# Emoji_Board_v2.net
KiCad netlist of a schematic drawn in EAGLE
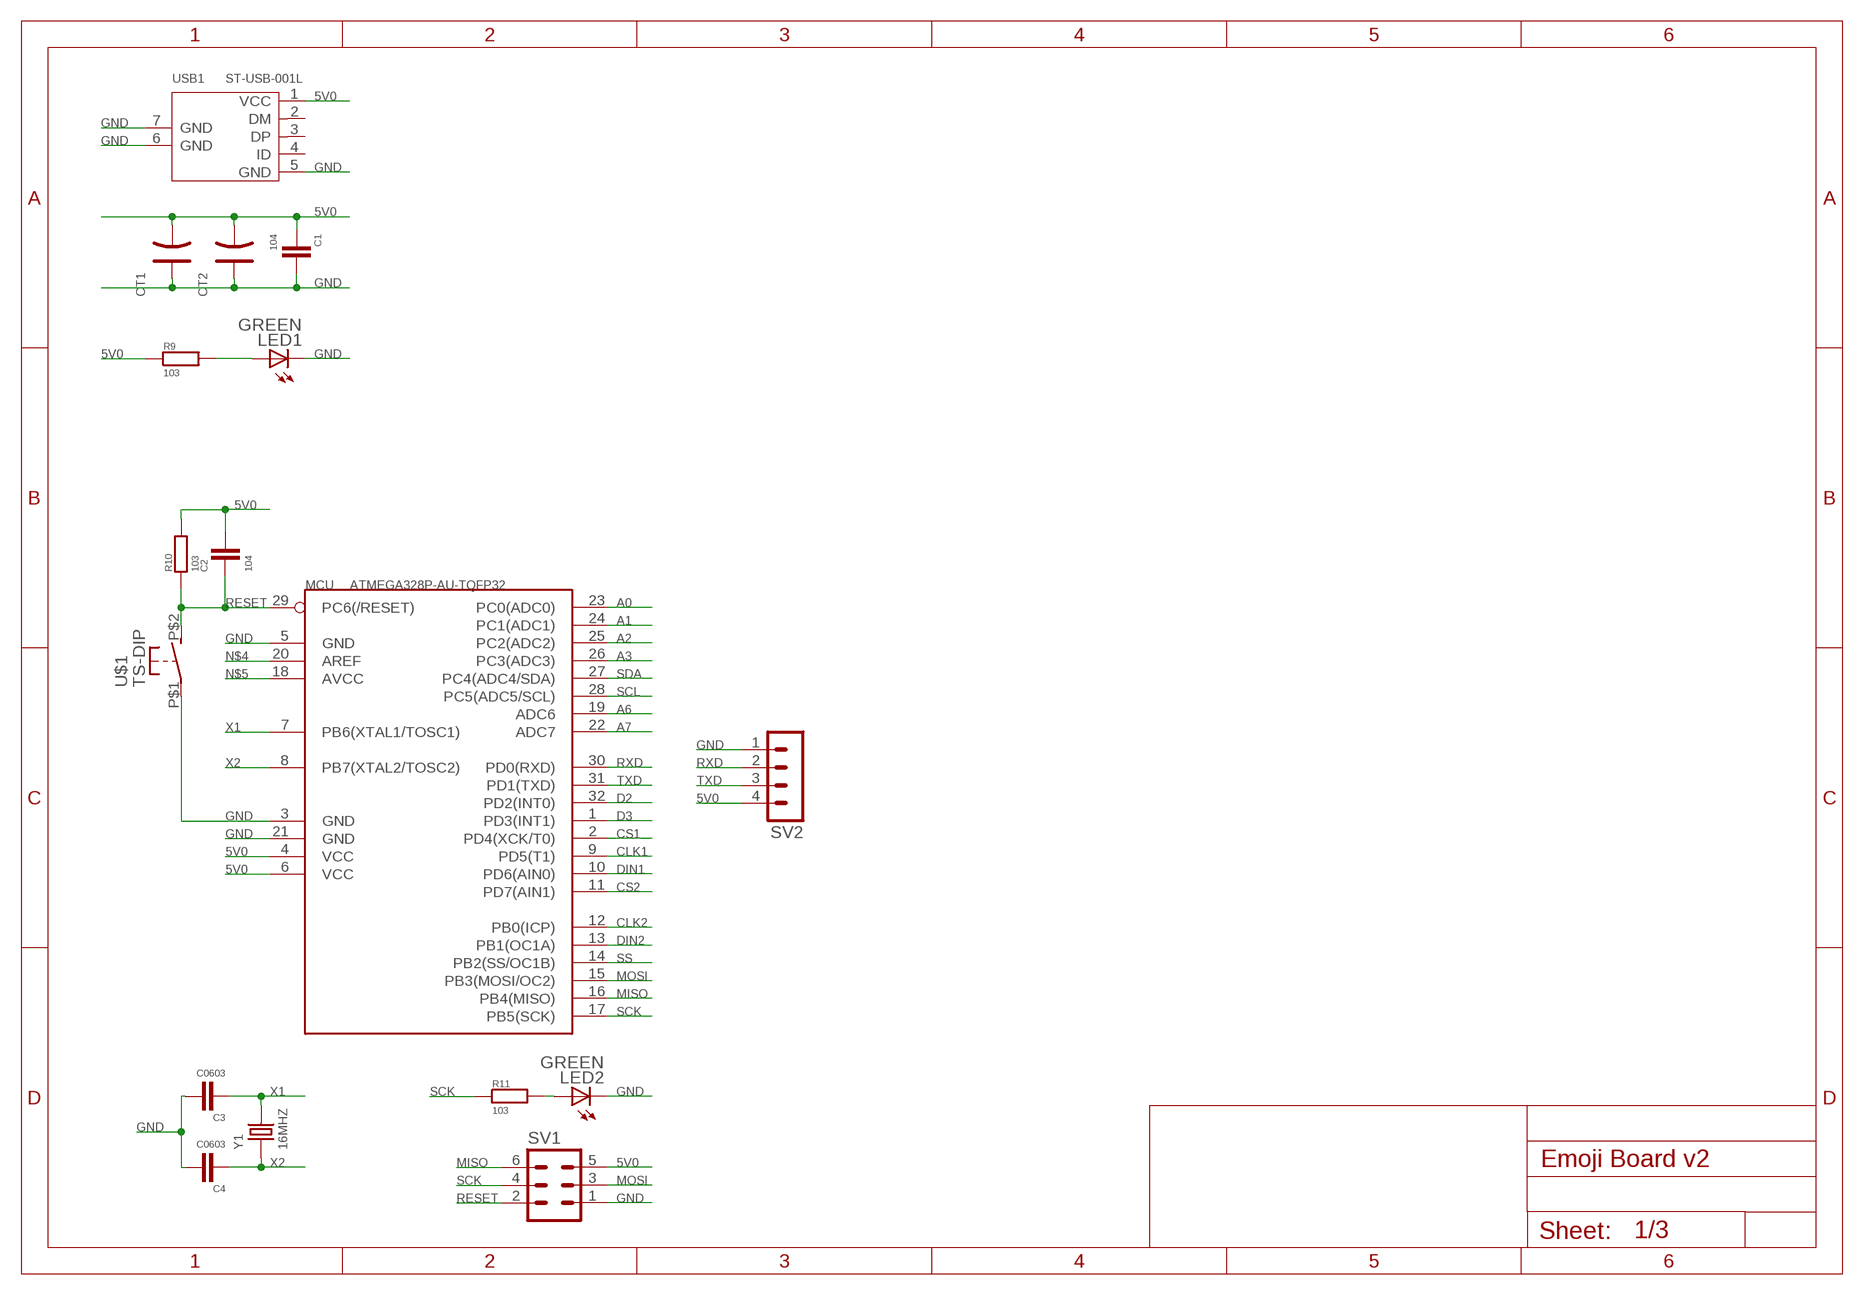
[diagram p0: schematic, sheet 1]
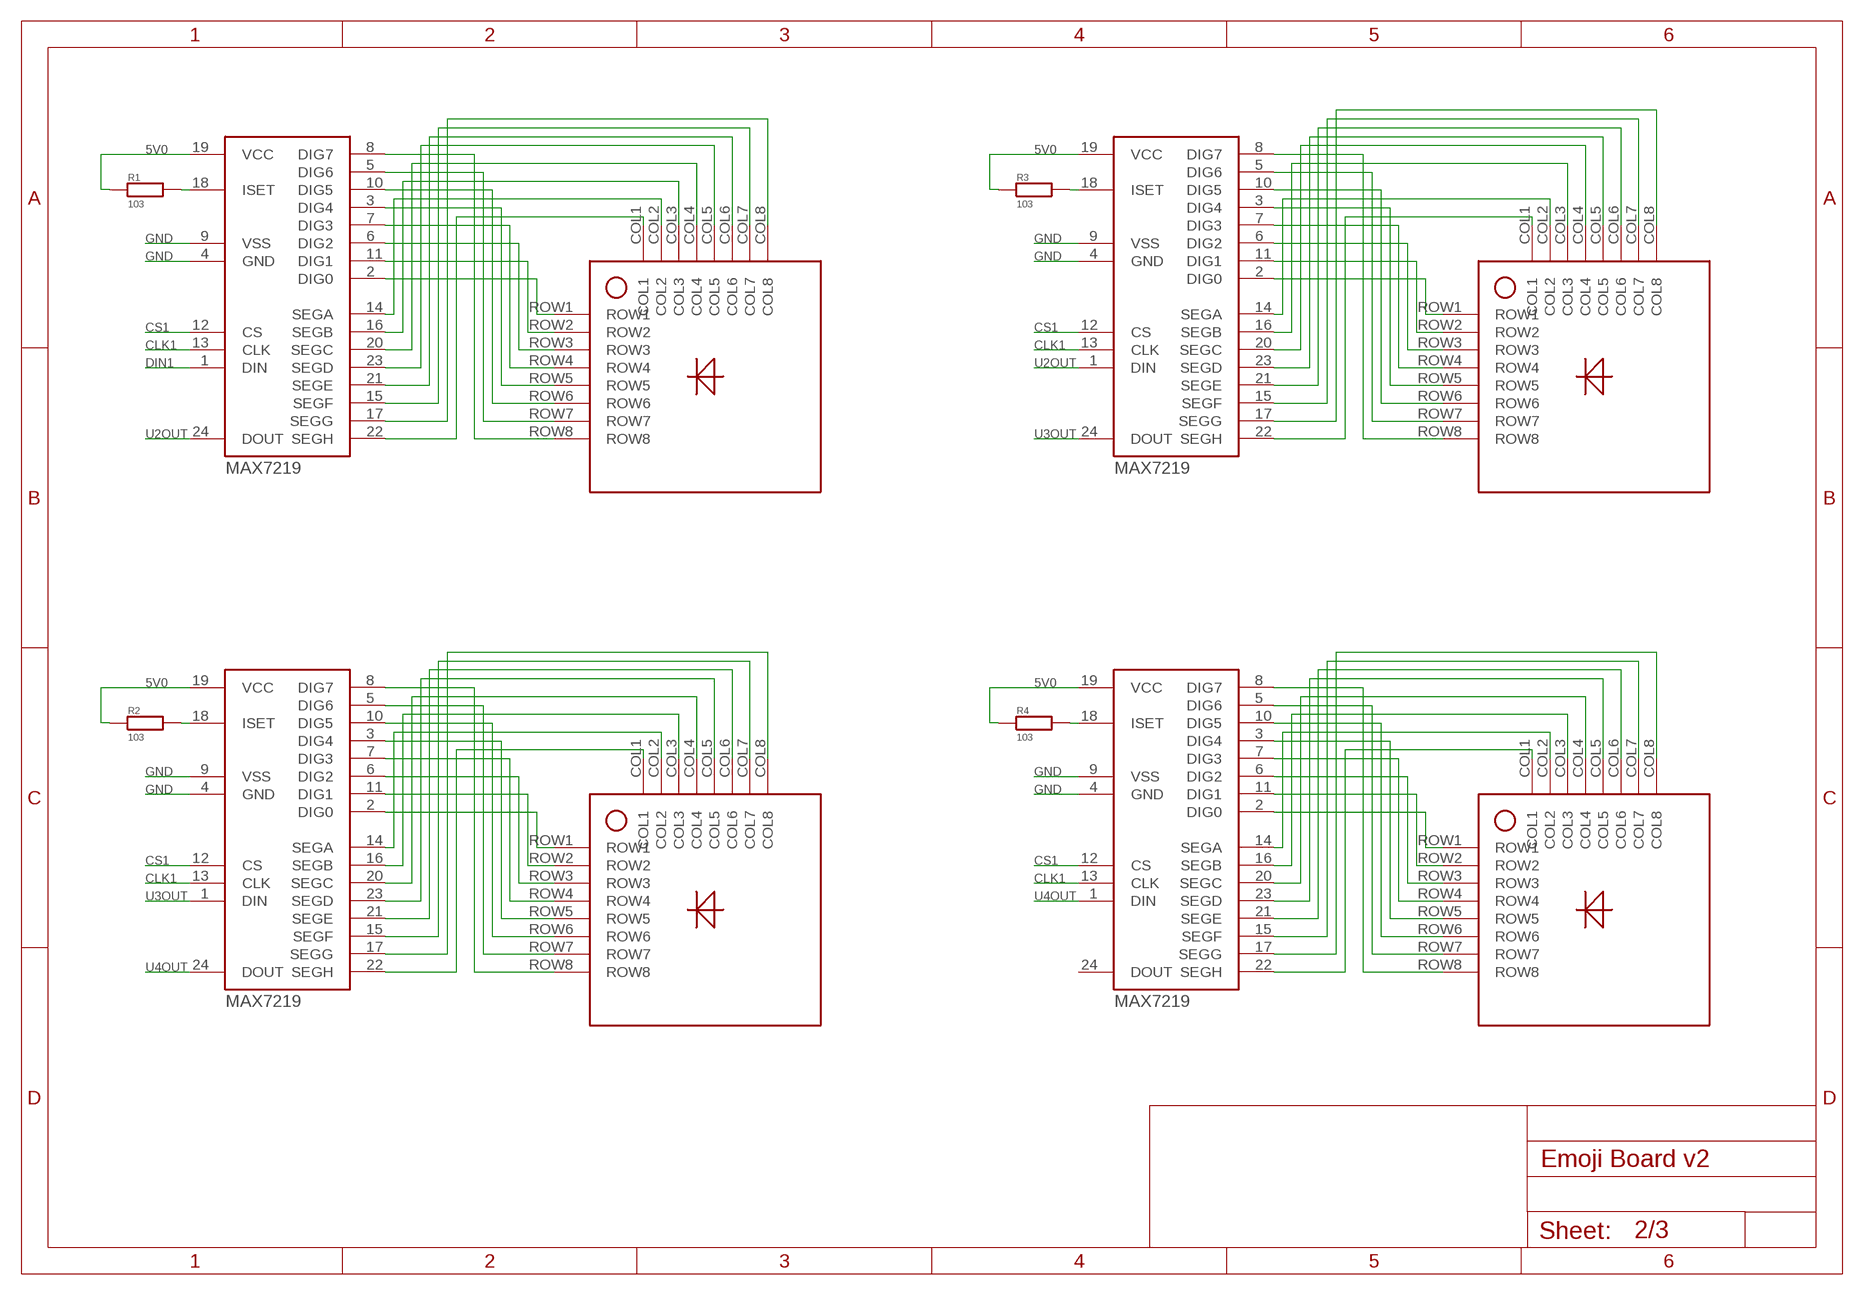
[diagram p1: schematic, sheet 2]
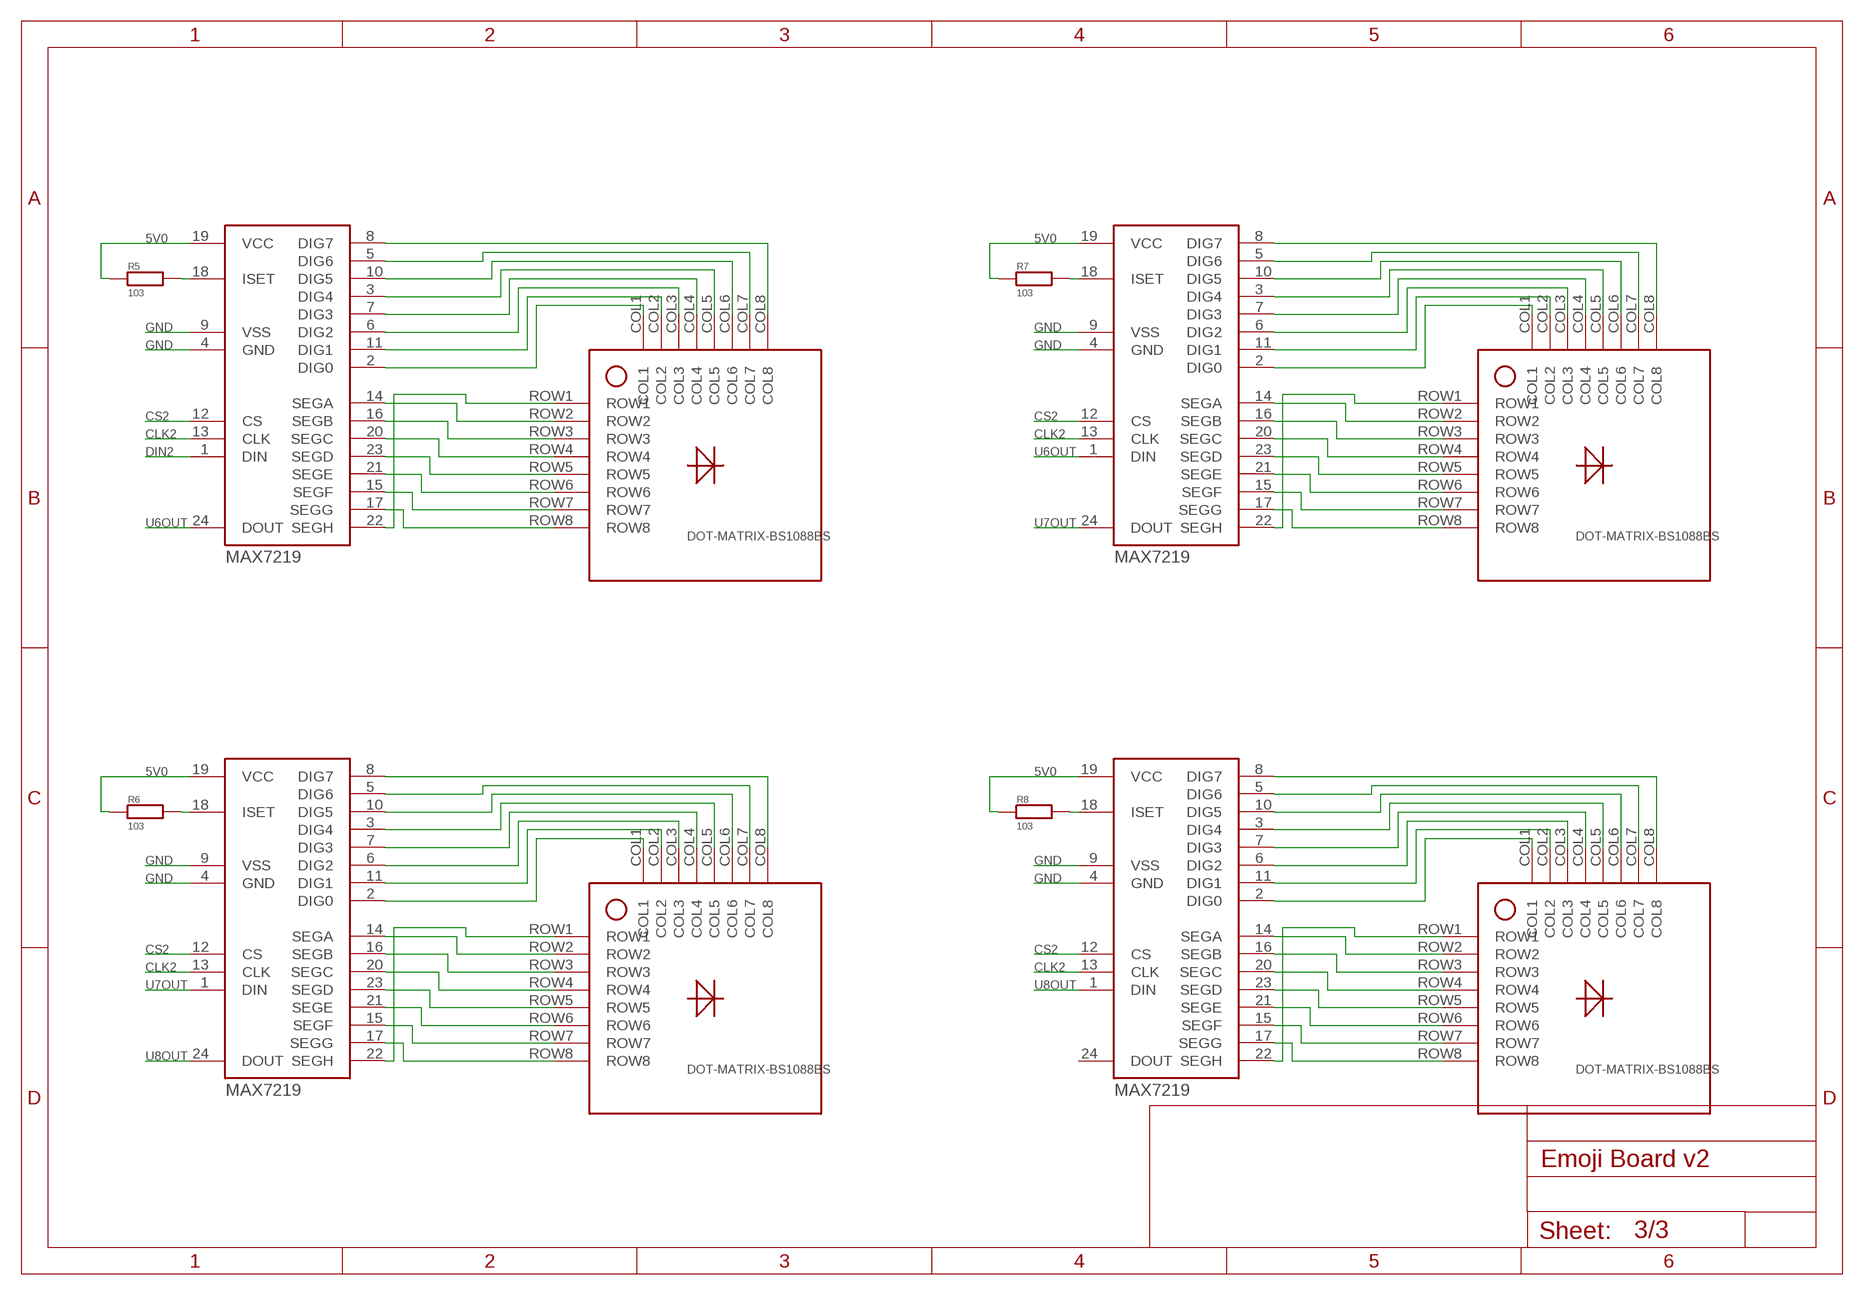
[diagram p2: schematic, sheet 3]

(export (version "E")
  (design (tool "Eeschema 10.0.6"))
  (components
    (comp (ref "R1")
      (value "103")
      (footprint "eagle-import:R0805")
      (libsource (lib "eagle-import") (part "R0805"))
    )
    (comp (ref "R2")
      (value "103")
      (footprint "eagle-import:R0805")
      (libsource (lib "eagle-import") (part "R0805"))
    )
    (comp (ref "R3")
      (value "103")
      (footprint "eagle-import:R0805")
      (libsource (lib "eagle-import") (part "R0805"))
    )
    (comp (ref "R4")
      (value "103")
      (footprint "eagle-import:R0805")
      (libsource (lib "eagle-import") (part "R0805"))
    )
    (comp (ref "T1")
      (value "DOT-MATRIX-AS")
      (footprint "eagle-import:1088AS")
      (libsource (lib "eagle-import") (part "DOT-MATRIX-AS"))
    )
    (comp (ref "T2")
      (value "DOT-MATRIX-AS")
      (footprint "eagle-import:1088AS")
      (libsource (lib "eagle-import") (part "DOT-MATRIX-AS"))
    )
    (comp (ref "T3")
      (value "DOT-MATRIX-AS")
      (footprint "eagle-import:1088AS")
      (libsource (lib "eagle-import") (part "DOT-MATRIX-AS"))
    )
    (comp (ref "T4")
      (value "DOT-MATRIX-AS")
      (footprint "eagle-import:1088AS")
      (libsource (lib "eagle-import") (part "DOT-MATRIX-AS"))
    )
    (comp (ref "U2")
      (value "MAX7219")
      (footprint "eagle-import:SOP24")
      (libsource (lib "eagle-import") (part "MAX7219"))
    )
    (comp (ref "U3")
      (value "MAX7219")
      (footprint "eagle-import:SOP24")
      (libsource (lib "eagle-import") (part "MAX7219"))
    )
    (comp (ref "U4")
      (value "MAX7219")
      (footprint "eagle-import:SOP24")
      (libsource (lib "eagle-import") (part "MAX7219"))
    )
    (comp (ref "U5")
      (value "MAX7219")
      (footprint "eagle-import:SOP24")
      (libsource (lib "eagle-import") (part "MAX7219"))
    )
    (comp (ref "C1")
      (value "104")
      (footprint "eagle-import:C0805")
      (libsource (lib "eagle-import") (part "C0805"))
    )
    (comp (ref "C2")
      (value "104")
      (footprint "eagle-import:C0805")
      (libsource (lib "eagle-import") (part "C0805"))
    )
    (comp (ref "C3")
      (value "C0603")
      (footprint "eagle-import:C0603")
      (libsource (lib "eagle-import") (part "C0603"))
    )
    (comp (ref "C4")
      (value "C0603")
      (footprint "eagle-import:C0603")
      (libsource (lib "eagle-import") (part "C0603"))
    )
    (comp (ref "CT1")
      (value "ALUMINUM-SMD-100UF-50V(D6.0-H6.0MM)")
      (footprint "eagle-import:ELECTRO-SMD-C-6.0MM")
      (fields (field (name "MPN") "CS1H101M-CRE77"))
      (libsource (lib "eagle-import") (part "ALUMINUM-SMD-100UF-50V(D6.0-H6.0MM)"))
    )
    (comp (ref "CT2")
      (value "ALUMINUM-SMD-100UF-50V(D6.0-H6.0MM)")
      (footprint "eagle-import:ELECTRO-SMD-C-6.0MM")
      (fields (field (name "MPN") "CS1H101M-CRE77"))
      (libsource (lib "eagle-import") (part "ALUMINUM-SMD-100UF-50V(D6.0-H6.0MM)"))
    )
    (comp (ref "LED1")
      (value "GREEN")
      (footprint "eagle-import:LED0805")
      (libsource (lib "eagle-import") (part "LEDCHIPLED_0805"))
    )
    (comp (ref "LED2")
      (value "GREEN")
      (footprint "eagle-import:LED0805")
      (libsource (lib "eagle-import") (part "LEDCHIPLED_0805"))
    )
    (comp (ref "MCU")
      (value "ATMEGA328P-AU-TQFP32")
      (footprint "eagle-import:TQFP32")
      (fields (field (name "MPN") "ATMEGA328P-AU"))
      (libsource (lib "eagle-import") (part "ATMEGA328P-AU"))
    )
    (comp (ref "R9")
      (value "103")
      (footprint "eagle-import:R0805")
      (libsource (lib "eagle-import") (part "R0805"))
    )
    (comp (ref "R10")
      (value "103")
      (footprint "eagle-import:R0805")
      (libsource (lib "eagle-import") (part "R0805"))
    )
    (comp (ref "R11")
      (value "103")
      (footprint "eagle-import:R0805")
      (libsource (lib "eagle-import") (part "R0805"))
    )
    (comp (ref "SV1")
      (value "MA03-2")
      (footprint "eagle-import:MA03-2")
      (libsource (lib "eagle-import") (part "MA03-2"))
    )
    (comp (ref "SV2")
      (value "MA04-1")
      (footprint "eagle-import:MA04-1")
      (libsource (lib "eagle-import") (part "MA04-1"))
    )
    (comp (ref "U$1")
      (value "TS-DIP")
      (footprint "eagle-import:TS-DIP")
      (libsource (lib "eagle-import") (part "TS-DIP"))
    )
    (comp (ref "USB1")
      (value "ST-USB-001L")
      (footprint "eagle-import:MICRO-USB-SMD-5+2")
      (libsource (lib "eagle-import") (part "MICRO-USB-SMD-5+2"))
    )
    (comp (ref "Y1")
      (value "16MHZ")
      (footprint "eagle-import:HC49US")
      (fields (field (name "MPN") "HC-49US    16.000MHz"))
      (libsource (lib "eagle-import") (part "DIP-CRYSTAL-16MHZ-18PF-30PPM-40R(HC49US)"))
    )
    (comp (ref "R5")
      (value "103")
      (footprint "eagle-import:R0805")
      (libsource (lib "eagle-import") (part "R0805"))
    )
    (comp (ref "R6")
      (value "103")
      (footprint "eagle-import:R0805")
      (libsource (lib "eagle-import") (part "R0805"))
    )
    (comp (ref "R7")
      (value "103")
      (footprint "eagle-import:R0805")
      (libsource (lib "eagle-import") (part "R0805"))
    )
    (comp (ref "R8")
      (value "103")
      (footprint "eagle-import:R0805")
      (libsource (lib "eagle-import") (part "R0805"))
    )
    (comp (ref "T5")
      (value "DOT-MATRIX-BS1088BS")
      (footprint "eagle-import:1088BS")
      (libsource (lib "eagle-import") (part "DOT-MATRIX-BS1088BS"))
    )
    (comp (ref "T6")
      (value "DOT-MATRIX-BS1088BS")
      (footprint "eagle-import:1088BS")
      (libsource (lib "eagle-import") (part "DOT-MATRIX-BS1088BS"))
    )
    (comp (ref "T7")
      (value "DOT-MATRIX-BS1088BS")
      (footprint "eagle-import:1088BS")
      (libsource (lib "eagle-import") (part "DOT-MATRIX-BS1088BS"))
    )
    (comp (ref "T8")
      (value "DOT-MATRIX-BS1088BS")
      (footprint "eagle-import:1088BS")
      (libsource (lib "eagle-import") (part "DOT-MATRIX-BS1088BS"))
    )
    (comp (ref "U6")
      (value "MAX7219")
      (footprint "eagle-import:SOP24")
      (libsource (lib "eagle-import") (part "MAX7219"))
    )
    (comp (ref "U7")
      (value "MAX7219")
      (footprint "eagle-import:SOP24")
      (libsource (lib "eagle-import") (part "MAX7219"))
    )
    (comp (ref "U8")
      (value "MAX7219")
      (footprint "eagle-import:SOP24")
      (libsource (lib "eagle-import") (part "MAX7219"))
    )
    (comp (ref "U9")
      (value "MAX7219")
      (footprint "eagle-import:SOP24")
      (libsource (lib "eagle-import") (part "MAX7219"))
    )
  )
  (nets
    (net (code "1") (name "5V0") (class "Default")
      (node (ref "C1") (pin "2") (pinfunction "2_2") (pintype "bidirectional"))
      (node (ref "C2") (pin "1") (pinfunction "1_1") (pintype "bidirectional"))
      (node (ref "CT1") (pin "-") (pinfunction "-_-") (pintype "passive"))
      (node (ref "CT2") (pin "-") (pinfunction "-_-") (pintype "passive"))
      (node (ref "MCU") (pin "4") (pinfunction "VCC_4") (pintype "bidirectional"))
      (node (ref "MCU") (pin "6") (pinfunction "VCC_6") (pintype "bidirectional"))
      (node (ref "R1") (pin "1") (pinfunction "1_1") (pintype "bidirectional"))
      (node (ref "R10") (pin "2") (pinfunction "2_2") (pintype "bidirectional"))
      (node (ref "R2") (pin "1") (pinfunction "1_1") (pintype "bidirectional"))
      (node (ref "R3") (pin "1") (pinfunction "1_1") (pintype "bidirectional"))
      (node (ref "R4") (pin "1") (pinfunction "1_1") (pintype "bidirectional"))
      (node (ref "R5") (pin "1") (pinfunction "1_1") (pintype "bidirectional"))
      (node (ref "R6") (pin "1") (pinfunction "1_1") (pintype "bidirectional"))
      (node (ref "R7") (pin "1") (pinfunction "1_1") (pintype "bidirectional"))
      (node (ref "R8") (pin "1") (pinfunction "1_1") (pintype "bidirectional"))
      (node (ref "R9") (pin "1") (pinfunction "1_1") (pintype "bidirectional"))
      (node (ref "SV1") (pin "5") (pinfunction "5_5") (pintype "passive"))
      (node (ref "SV2") (pin "4") (pinfunction "4_4") (pintype "passive"))
      (node (ref "U2") (pin "19") (pinfunction "VCC_19") (pintype "power_in"))
      (node (ref "U3") (pin "19") (pinfunction "VCC_19") (pintype "power_in"))
      (node (ref "U4") (pin "19") (pinfunction "VCC_19") (pintype "power_in"))
      (node (ref "U5") (pin "19") (pinfunction "VCC_19") (pintype "power_in"))
      (node (ref "U6") (pin "19") (pinfunction "VCC_19") (pintype "power_in"))
      (node (ref "U7") (pin "19") (pinfunction "VCC_19") (pintype "power_in"))
      (node (ref "U8") (pin "19") (pinfunction "VCC_19") (pintype "power_in"))
      (node (ref "U9") (pin "19") (pinfunction "VCC_19") (pintype "power_in"))
      (node (ref "USB1") (pin "1") (pinfunction "VCC_1") (pintype "bidirectional"))
    )
    (net (code "2") (name "A0") (class "Default")
      (node (ref "MCU") (pin "23") (pinfunction "PC0(ADC0)_23") (pintype "bidirectional"))
    )
    (net (code "3") (name "A1") (class "Default")
      (node (ref "MCU") (pin "24") (pinfunction "PC1(ADC1)_24") (pintype "bidirectional"))
    )
    (net (code "4") (name "A2") (class "Default")
      (node (ref "MCU") (pin "25") (pinfunction "PC2(ADC2)_25") (pintype "bidirectional"))
    )
    (net (code "5") (name "A3") (class "Default")
      (node (ref "MCU") (pin "26") (pinfunction "PC3(ADC3)_26") (pintype "bidirectional"))
    )
    (net (code "6") (name "A6") (class "Default")
      (node (ref "MCU") (pin "19") (pinfunction "ADC6_19") (pintype "bidirectional"))
    )
    (net (code "7") (name "A7") (class "Default")
      (node (ref "MCU") (pin "22") (pinfunction "ADC7_22") (pintype "bidirectional"))
    )
    (net (code "8") (name "CLK1") (class "Default")
      (node (ref "MCU") (pin "9") (pinfunction "PD5(T1)_9") (pintype "bidirectional"))
      (node (ref "U2") (pin "13") (pinfunction "CLK_13") (pintype "input"))
      (node (ref "U3") (pin "13") (pinfunction "CLK_13") (pintype "input"))
      (node (ref "U4") (pin "13") (pinfunction "CLK_13") (pintype "input"))
      (node (ref "U5") (pin "13") (pinfunction "CLK_13") (pintype "input"))
    )
    (net (code "9") (name "CLK2") (class "Default")
      (node (ref "MCU") (pin "12") (pinfunction "PB0(ICP)_12") (pintype "bidirectional"))
      (node (ref "U6") (pin "13") (pinfunction "CLK_13") (pintype "input"))
      (node (ref "U7") (pin "13") (pinfunction "CLK_13") (pintype "input"))
      (node (ref "U8") (pin "13") (pinfunction "CLK_13") (pintype "input"))
      (node (ref "U9") (pin "13") (pinfunction "CLK_13") (pintype "input"))
    )
    (net (code "10") (name "CS1") (class "Default")
      (node (ref "MCU") (pin "2") (pinfunction "PD4(XCK/T0)_2") (pintype "bidirectional"))
      (node (ref "U2") (pin "12") (pinfunction "CS_12") (pintype "input"))
      (node (ref "U3") (pin "12") (pinfunction "CS_12") (pintype "input"))
      (node (ref "U4") (pin "12") (pinfunction "CS_12") (pintype "input"))
      (node (ref "U5") (pin "12") (pinfunction "CS_12") (pintype "input"))
    )
    (net (code "11") (name "CS2") (class "Default")
      (node (ref "MCU") (pin "11") (pinfunction "PD7(AIN1)_11") (pintype "bidirectional"))
      (node (ref "U6") (pin "12") (pinfunction "CS_12") (pintype "input"))
      (node (ref "U7") (pin "12") (pinfunction "CS_12") (pintype "input"))
      (node (ref "U8") (pin "12") (pinfunction "CS_12") (pintype "input"))
      (node (ref "U9") (pin "12") (pinfunction "CS_12") (pintype "input"))
    )
    (net (code "12") (name "D2") (class "Default")
      (node (ref "MCU") (pin "32") (pinfunction "PD2(INT0)_32") (pintype "bidirectional"))
    )
    (net (code "13") (name "D3") (class "Default")
      (node (ref "MCU") (pin "1") (pinfunction "PD3(INT1)_1") (pintype "bidirectional"))
    )
    (net (code "14") (name "DIN1") (class "Default")
      (node (ref "MCU") (pin "10") (pinfunction "PD6(AIN0)_10") (pintype "bidirectional"))
      (node (ref "U2") (pin "1") (pinfunction "DIN_1") (pintype "input"))
    )
    (net (code "15") (name "DIN2") (class "Default")
      (node (ref "MCU") (pin "13") (pinfunction "PB1(OC1A)_13") (pintype "bidirectional"))
      (node (ref "U6") (pin "1") (pinfunction "DIN_1") (pintype "input"))
    )
    (net (code "16") (name "GND") (class "Default")
      (node (ref "C1") (pin "1") (pinfunction "1_1") (pintype "bidirectional"))
      (node (ref "C3") (pin "1") (pinfunction "1_1") (pintype "bidirectional"))
      (node (ref "C4") (pin "1") (pinfunction "1_1") (pintype "bidirectional"))
      (node (ref "CT1") (pin "+") (pinfunction "+_+") (pintype "passive"))
      (node (ref "CT2") (pin "+") (pinfunction "+_+") (pintype "passive"))
      (node (ref "LED1") (pin "C") (pinfunction "C_C") (pintype "passive"))
      (node (ref "LED2") (pin "C") (pinfunction "C_C") (pintype "passive"))
      (node (ref "MCU") (pin "21") (pinfunction "GND_21") (pintype "bidirectional"))
      (node (ref "MCU") (pin "3") (pinfunction "GND_3") (pintype "bidirectional"))
      (node (ref "MCU") (pin "5") (pinfunction "GND_5") (pintype "bidirectional"))
      (node (ref "SV1") (pin "1") (pinfunction "1_1") (pintype "passive"))
      (node (ref "SV2") (pin "1") (pinfunction "1_1") (pintype "passive"))
      (node (ref "U$1") (pin "P$1") (pinfunction "P_P$1") (pintype "passive"))
      (node (ref "U2") (pin "4") (pinfunction "GND_4") (pintype "power_in"))
      (node (ref "U2") (pin "9") (pinfunction "VSS_9") (pintype "power_in"))
      (node (ref "U3") (pin "4") (pinfunction "GND_4") (pintype "power_in"))
      (node (ref "U3") (pin "9") (pinfunction "VSS_9") (pintype "power_in"))
      (node (ref "U4") (pin "4") (pinfunction "GND_4") (pintype "power_in"))
      (node (ref "U4") (pin "9") (pinfunction "VSS_9") (pintype "power_in"))
      (node (ref "U5") (pin "4") (pinfunction "GND_4") (pintype "power_in"))
      (node (ref "U5") (pin "9") (pinfunction "VSS_9") (pintype "power_in"))
      (node (ref "U6") (pin "4") (pinfunction "GND_4") (pintype "power_in"))
      (node (ref "U6") (pin "9") (pinfunction "VSS_9") (pintype "power_in"))
      (node (ref "U7") (pin "4") (pinfunction "GND_4") (pintype "power_in"))
      (node (ref "U7") (pin "9") (pinfunction "VSS_9") (pintype "power_in"))
      (node (ref "U8") (pin "4") (pinfunction "GND_4") (pintype "power_in"))
      (node (ref "U8") (pin "9") (pinfunction "VSS_9") (pintype "power_in"))
      (node (ref "U9") (pin "4") (pinfunction "GND_4") (pintype "power_in"))
      (node (ref "U9") (pin "9") (pinfunction "VSS_9") (pintype "power_in"))
      (node (ref "USB1") (pin "5") (pinfunction "GND_5") (pintype "bidirectional"))
      (node (ref "USB1") (pin "6") (pinfunction "GND_6") (pintype "bidirectional"))
      (node (ref "USB1") (pin "7") (pinfunction "GND_7") (pintype "bidirectional"))
    )
    (net (code "17") (name "MISO") (class "Default")
      (node (ref "MCU") (pin "16") (pinfunction "PB4(MISO)_16") (pintype "bidirectional"))
      (node (ref "SV1") (pin "6") (pinfunction "6_6") (pintype "passive"))
    )
    (net (code "18") (name "MOSI") (class "Default")
      (node (ref "MCU") (pin "15") (pinfunction "PB3(MOSI/OC2)_15") (pintype "bidirectional"))
      (node (ref "SV1") (pin "3") (pinfunction "3_3") (pintype "passive"))
    )
    (net (code "19") (name "N$4") (class "Default")
      (node (ref "MCU") (pin "20") (pinfunction "AREF_20") (pintype "bidirectional"))
    )
    (net (code "20") (name "N$5") (class "Default")
      (node (ref "MCU") (pin "18") (pinfunction "AVCC_18") (pintype "bidirectional"))
    )
    (net (code "21") (name "Net-(LED1-PadA)") (class "Default")
      (node (ref "LED1") (pin "A") (pinfunction "A_A") (pintype "passive"))
      (node (ref "R9") (pin "2") (pinfunction "2_2") (pintype "bidirectional"))
    )
    (net (code "22") (name "Net-(LED2-PadA)") (class "Default")
      (node (ref "LED2") (pin "A") (pinfunction "A_A") (pintype "passive"))
      (node (ref "R11") (pin "2") (pinfunction "2_2") (pintype "bidirectional"))
    )
    (net (code "23") (name "Net-(U2-DIG0)") (class "Default")
      (node (ref "T1") (pin "ROW1") (pinfunction "ROW1_ROW1") (pintype "bidirectional"))
      (node (ref "U2") (pin "2") (pinfunction "DIG0_2") (pintype "input"))
    )
    (net (code "24") (name "Net-(U2-DIG1)") (class "Default")
      (node (ref "T1") (pin "ROW2") (pinfunction "ROW2_ROW2") (pintype "bidirectional"))
      (node (ref "U2") (pin "11") (pinfunction "DIG1_11") (pintype "input"))
    )
    (net (code "25") (name "Net-(U2-DIG2)") (class "Default")
      (node (ref "T1") (pin "ROW3") (pinfunction "ROW3_ROW3") (pintype "bidirectional"))
      (node (ref "U2") (pin "6") (pinfunction "DIG2_6") (pintype "input"))
    )
    (net (code "26") (name "Net-(U2-DIG3)") (class "Default")
      (node (ref "T1") (pin "ROW4") (pinfunction "ROW4_ROW4") (pintype "bidirectional"))
      (node (ref "U2") (pin "7") (pinfunction "DIG3_7") (pintype "input"))
    )
    (net (code "27") (name "Net-(U2-DIG4)") (class "Default")
      (node (ref "T1") (pin "ROW5") (pinfunction "ROW5_ROW5") (pintype "bidirectional"))
      (node (ref "U2") (pin "3") (pinfunction "DIG4_3") (pintype "input"))
    )
    (net (code "28") (name "Net-(U2-DIG5)") (class "Default")
      (node (ref "T1") (pin "ROW6") (pinfunction "ROW6_ROW6") (pintype "bidirectional"))
      (node (ref "U2") (pin "10") (pinfunction "DIG5_10") (pintype "input"))
    )
    (net (code "29") (name "Net-(U2-DIG6)") (class "Default")
      (node (ref "T1") (pin "ROW7") (pinfunction "ROW7_ROW7") (pintype "bidirectional"))
      (node (ref "U2") (pin "5") (pinfunction "DIG6_5") (pintype "input"))
    )
    (net (code "30") (name "Net-(U2-DIG7)") (class "Default")
      (node (ref "T1") (pin "ROW8") (pinfunction "ROW8_ROW8") (pintype "bidirectional"))
      (node (ref "U2") (pin "8") (pinfunction "DIG7_8") (pintype "input"))
    )
    (net (code "31") (name "Net-(U2-ISET)") (class "Default")
      (node (ref "R1") (pin "2") (pinfunction "2_2") (pintype "bidirectional"))
      (node (ref "U2") (pin "18") (pinfunction "ISET_18") (pintype "input"))
    )
    (net (code "32") (name "Net-(U2-SEGA)") (class "Default")
      (node (ref "T1") (pin "COL2") (pinfunction "COL2_COL2") (pintype "bidirectional"))
      (node (ref "U2") (pin "14") (pinfunction "SEGA_14") (pintype "input"))
    )
    (net (code "33") (name "Net-(U2-SEGB)") (class "Default")
      (node (ref "T1") (pin "COL3") (pinfunction "COL3_COL3") (pintype "bidirectional"))
      (node (ref "U2") (pin "16") (pinfunction "SEGB_16") (pintype "input"))
    )
    (net (code "34") (name "Net-(U2-SEGC)") (class "Default")
      (node (ref "T1") (pin "COL4") (pinfunction "COL4_COL4") (pintype "bidirectional"))
      (node (ref "U2") (pin "20") (pinfunction "SEGC_20") (pintype "input"))
    )
    (net (code "35") (name "Net-(U2-SEGD)") (class "Default")
      (node (ref "T1") (pin "COL5") (pinfunction "COL5_COL5") (pintype "bidirectional"))
      (node (ref "U2") (pin "23") (pinfunction "SEGD_23") (pintype "input"))
    )
    (net (code "36") (name "Net-(U2-SEGE)") (class "Default")
      (node (ref "T1") (pin "COL6") (pinfunction "COL6_COL6") (pintype "bidirectional"))
      (node (ref "U2") (pin "21") (pinfunction "SEGE_21") (pintype "input"))
    )
    (net (code "37") (name "Net-(U2-SEGF)") (class "Default")
      (node (ref "T1") (pin "COL7") (pinfunction "COL7_COL7") (pintype "bidirectional"))
      (node (ref "U2") (pin "15") (pinfunction "SEGF_15") (pintype "input"))
    )
    (net (code "38") (name "Net-(U2-SEGG)") (class "Default")
      (node (ref "T1") (pin "COL8") (pinfunction "COL8_COL8") (pintype "bidirectional"))
      (node (ref "U2") (pin "17") (pinfunction "SEGG_17") (pintype "input"))
    )
    (net (code "39") (name "Net-(U2-SEGH)") (class "Default")
      (node (ref "T1") (pin "COL1") (pinfunction "COL1_COL1") (pintype "bidirectional"))
      (node (ref "U2") (pin "22") (pinfunction "SEGH_22") (pintype "input"))
    )
    (net (code "40") (name "Net-(U3-DIG0)") (class "Default")
      (node (ref "T2") (pin "ROW1") (pinfunction "ROW1_ROW1") (pintype "bidirectional"))
      (node (ref "U3") (pin "2") (pinfunction "DIG0_2") (pintype "input"))
    )
    (net (code "41") (name "Net-(U3-DIG1)") (class "Default")
      (node (ref "T2") (pin "ROW2") (pinfunction "ROW2_ROW2") (pintype "bidirectional"))
      (node (ref "U3") (pin "11") (pinfunction "DIG1_11") (pintype "input"))
    )
    (net (code "42") (name "Net-(U3-DIG2)") (class "Default")
      (node (ref "T2") (pin "ROW3") (pinfunction "ROW3_ROW3") (pintype "bidirectional"))
      (node (ref "U3") (pin "6") (pinfunction "DIG2_6") (pintype "input"))
    )
    (net (code "43") (name "Net-(U3-DIG3)") (class "Default")
      (node (ref "T2") (pin "ROW4") (pinfunction "ROW4_ROW4") (pintype "bidirectional"))
      (node (ref "U3") (pin "7") (pinfunction "DIG3_7") (pintype "input"))
    )
    (net (code "44") (name "Net-(U3-DIG4)") (class "Default")
      (node (ref "T2") (pin "ROW5") (pinfunction "ROW5_ROW5") (pintype "bidirectional"))
      (node (ref "U3") (pin "3") (pinfunction "DIG4_3") (pintype "input"))
    )
    (net (code "45") (name "Net-(U3-DIG5)") (class "Default")
      (node (ref "T2") (pin "ROW6") (pinfunction "ROW6_ROW6") (pintype "bidirectional"))
      (node (ref "U3") (pin "10") (pinfunction "DIG5_10") (pintype "input"))
    )
    (net (code "46") (name "Net-(U3-DIG6)") (class "Default")
      (node (ref "T2") (pin "ROW7") (pinfunction "ROW7_ROW7") (pintype "bidirectional"))
      (node (ref "U3") (pin "5") (pinfunction "DIG6_5") (pintype "input"))
    )
    (net (code "47") (name "Net-(U3-DIG7)") (class "Default")
      (node (ref "T2") (pin "ROW8") (pinfunction "ROW8_ROW8") (pintype "bidirectional"))
      (node (ref "U3") (pin "8") (pinfunction "DIG7_8") (pintype "input"))
    )
    (net (code "48") (name "Net-(U3-ISET)") (class "Default")
      (node (ref "R3") (pin "2") (pinfunction "2_2") (pintype "bidirectional"))
      (node (ref "U3") (pin "18") (pinfunction "ISET_18") (pintype "input"))
    )
    (net (code "49") (name "Net-(U3-SEGA)") (class "Default")
      (node (ref "T2") (pin "COL2") (pinfunction "COL2_COL2") (pintype "bidirectional"))
      (node (ref "U3") (pin "14") (pinfunction "SEGA_14") (pintype "input"))
    )
    (net (code "50") (name "Net-(U3-SEGB)") (class "Default")
      (node (ref "T2") (pin "COL3") (pinfunction "COL3_COL3") (pintype "bidirectional"))
      (node (ref "U3") (pin "16") (pinfunction "SEGB_16") (pintype "input"))
    )
    (net (code "51") (name "Net-(U3-SEGC)") (class "Default")
      (node (ref "T2") (pin "COL4") (pinfunction "COL4_COL4") (pintype "bidirectional"))
      (node (ref "U3") (pin "20") (pinfunction "SEGC_20") (pintype "input"))
    )
    (net (code "52") (name "Net-(U3-SEGD)") (class "Default")
      (node (ref "T2") (pin "COL5") (pinfunction "COL5_COL5") (pintype "bidirectional"))
      (node (ref "U3") (pin "23") (pinfunction "SEGD_23") (pintype "input"))
    )
    (net (code "53") (name "Net-(U3-SEGE)") (class "Default")
      (node (ref "T2") (pin "COL6") (pinfunction "COL6_COL6") (pintype "bidirectional"))
      (node (ref "U3") (pin "21") (pinfunction "SEGE_21") (pintype "input"))
    )
    (net (code "54") (name "Net-(U3-SEGF)") (class "Default")
      (node (ref "T2") (pin "COL7") (pinfunction "COL7_COL7") (pintype "bidirectional"))
      (node (ref "U3") (pin "15") (pinfunction "SEGF_15") (pintype "input"))
    )
    (net (code "55") (name "Net-(U3-SEGG)") (class "Default")
      (node (ref "T2") (pin "COL8") (pinfunction "COL8_COL8") (pintype "bidirectional"))
      (node (ref "U3") (pin "17") (pinfunction "SEGG_17") (pintype "input"))
    )
    (net (code "56") (name "Net-(U3-SEGH)") (class "Default")
      (node (ref "T2") (pin "COL1") (pinfunction "COL1_COL1") (pintype "bidirectional"))
      (node (ref "U3") (pin "22") (pinfunction "SEGH_22") (pintype "input"))
    )
    (net (code "57") (name "Net-(U4-DIG0)") (class "Default")
      (node (ref "T3") (pin "ROW1") (pinfunction "ROW1_ROW1") (pintype "bidirectional"))
      (node (ref "U4") (pin "2") (pinfunction "DIG0_2") (pintype "input"))
    )
    (net (code "58") (name "Net-(U4-DIG1)") (class "Default")
      (node (ref "T3") (pin "ROW2") (pinfunction "ROW2_ROW2") (pintype "bidirectional"))
      (node (ref "U4") (pin "11") (pinfunction "DIG1_11") (pintype "input"))
    )
    (net (code "59") (name "Net-(U4-DIG2)") (class "Default")
      (node (ref "T3") (pin "ROW3") (pinfunction "ROW3_ROW3") (pintype "bidirectional"))
      (node (ref "U4") (pin "6") (pinfunction "DIG2_6") (pintype "input"))
    )
    (net (code "60") (name "Net-(U4-DIG3)") (class "Default")
      (node (ref "T3") (pin "ROW4") (pinfunction "ROW4_ROW4") (pintype "bidirectional"))
      (node (ref "U4") (pin "7") (pinfunction "DIG3_7") (pintype "input"))
    )
    (net (code "61") (name "Net-(U4-DIG4)") (class "Default")
      (node (ref "T3") (pin "ROW5") (pinfunction "ROW5_ROW5") (pintype "bidirectional"))
      (node (ref "U4") (pin "3") (pinfunction "DIG4_3") (pintype "input"))
    )
    (net (code "62") (name "Net-(U4-DIG5)") (class "Default")
      (node (ref "T3") (pin "ROW6") (pinfunction "ROW6_ROW6") (pintype "bidirectional"))
      (node (ref "U4") (pin "10") (pinfunction "DIG5_10") (pintype "input"))
    )
    (net (code "63") (name "Net-(U4-DIG6)") (class "Default")
      (node (ref "T3") (pin "ROW7") (pinfunction "ROW7_ROW7") (pintype "bidirectional"))
      (node (ref "U4") (pin "5") (pinfunction "DIG6_5") (pintype "input"))
    )
    (net (code "64") (name "Net-(U4-DIG7)") (class "Default")
      (node (ref "T3") (pin "ROW8") (pinfunction "ROW8_ROW8") (pintype "bidirectional"))
      (node (ref "U4") (pin "8") (pinfunction "DIG7_8") (pintype "input"))
    )
    (net (code "65") (name "Net-(U4-ISET)") (class "Default")
      (node (ref "R2") (pin "2") (pinfunction "2_2") (pintype "bidirectional"))
      (node (ref "U4") (pin "18") (pinfunction "ISET_18") (pintype "input"))
    )
    (net (code "66") (name "Net-(U4-SEGA)") (class "Default")
      (node (ref "T3") (pin "COL2") (pinfunction "COL2_COL2") (pintype "bidirectional"))
      (node (ref "U4") (pin "14") (pinfunction "SEGA_14") (pintype "input"))
    )
    (net (code "67") (name "Net-(U4-SEGB)") (class "Default")
      (node (ref "T3") (pin "COL3") (pinfunction "COL3_COL3") (pintype "bidirectional"))
      (node (ref "U4") (pin "16") (pinfunction "SEGB_16") (pintype "input"))
    )
    (net (code "68") (name "Net-(U4-SEGC)") (class "Default")
      (node (ref "T3") (pin "COL4") (pinfunction "COL4_COL4") (pintype "bidirectional"))
      (node (ref "U4") (pin "20") (pinfunction "SEGC_20") (pintype "input"))
    )
    (net (code "69") (name "Net-(U4-SEGD)") (class "Default")
      (node (ref "T3") (pin "COL5") (pinfunction "COL5_COL5") (pintype "bidirectional"))
      (node (ref "U4") (pin "23") (pinfunction "SEGD_23") (pintype "input"))
    )
    (net (code "70") (name "Net-(U4-SEGE)") (class "Default")
      (node (ref "T3") (pin "COL6") (pinfunction "COL6_COL6") (pintype "bidirectional"))
      (node (ref "U4") (pin "21") (pinfunction "SEGE_21") (pintype "input"))
    )
    (net (code "71") (name "Net-(U4-SEGF)") (class "Default")
      (node (ref "T3") (pin "COL7") (pinfunction "COL7_COL7") (pintype "bidirectional"))
      (node (ref "U4") (pin "15") (pinfunction "SEGF_15") (pintype "input"))
    )
    (net (code "72") (name "Net-(U4-SEGG)") (class "Default")
      (node (ref "T3") (pin "COL8") (pinfunction "COL8_COL8") (pintype "bidirectional"))
      (node (ref "U4") (pin "17") (pinfunction "SEGG_17") (pintype "input"))
    )
    (net (code "73") (name "Net-(U4-SEGH)") (class "Default")
      (node (ref "T3") (pin "COL1") (pinfunction "COL1_COL1") (pintype "bidirectional"))
      (node (ref "U4") (pin "22") (pinfunction "SEGH_22") (pintype "input"))
    )
    (net (code "74") (name "Net-(U5-DIG0)") (class "Default")
      (node (ref "T4") (pin "ROW1") (pinfunction "ROW1_ROW1") (pintype "bidirectional"))
      (node (ref "U5") (pin "2") (pinfunction "DIG0_2") (pintype "input"))
    )
    (net (code "75") (name "Net-(U5-DIG1)") (class "Default")
      (node (ref "T4") (pin "ROW2") (pinfunction "ROW2_ROW2") (pintype "bidirectional"))
      (node (ref "U5") (pin "11") (pinfunction "DIG1_11") (pintype "input"))
    )
    (net (code "76") (name "Net-(U5-DIG2)") (class "Default")
      (node (ref "T4") (pin "ROW3") (pinfunction "ROW3_ROW3") (pintype "bidirectional"))
      (node (ref "U5") (pin "6") (pinfunction "DIG2_6") (pintype "input"))
    )
    (net (code "77") (name "Net-(U5-DIG3)") (class "Default")
      (node (ref "T4") (pin "ROW4") (pinfunction "ROW4_ROW4") (pintype "bidirectional"))
      (node (ref "U5") (pin "7") (pinfunction "DIG3_7") (pintype "input"))
    )
    (net (code "78") (name "Net-(U5-DIG4)") (class "Default")
      (node (ref "T4") (pin "ROW5") (pinfunction "ROW5_ROW5") (pintype "bidirectional"))
      (node (ref "U5") (pin "3") (pinfunction "DIG4_3") (pintype "input"))
    )
    (net (code "79") (name "Net-(U5-DIG5)") (class "Default")
      (node (ref "T4") (pin "ROW6") (pinfunction "ROW6_ROW6") (pintype "bidirectional"))
      (node (ref "U5") (pin "10") (pinfunction "DIG5_10") (pintype "input"))
    )
    (net (code "80") (name "Net-(U5-DIG6)") (class "Default")
      (node (ref "T4") (pin "ROW7") (pinfunction "ROW7_ROW7") (pintype "bidirectional"))
      (node (ref "U5") (pin "5") (pinfunction "DIG6_5") (pintype "input"))
    )
    (net (code "81") (name "Net-(U5-DIG7)") (class "Default")
      (node (ref "T4") (pin "ROW8") (pinfunction "ROW8_ROW8") (pintype "bidirectional"))
      (node (ref "U5") (pin "8") (pinfunction "DIG7_8") (pintype "input"))
    )
    (net (code "82") (name "Net-(U5-ISET)") (class "Default")
      (node (ref "R4") (pin "2") (pinfunction "2_2") (pintype "bidirectional"))
      (node (ref "U5") (pin "18") (pinfunction "ISET_18") (pintype "input"))
    )
    (net (code "83") (name "Net-(U5-SEGA)") (class "Default")
      (node (ref "T4") (pin "COL2") (pinfunction "COL2_COL2") (pintype "bidirectional"))
      (node (ref "U5") (pin "14") (pinfunction "SEGA_14") (pintype "input"))
    )
    (net (code "84") (name "Net-(U5-SEGB)") (class "Default")
      (node (ref "T4") (pin "COL3") (pinfunction "COL3_COL3") (pintype "bidirectional"))
      (node (ref "U5") (pin "16") (pinfunction "SEGB_16") (pintype "input"))
    )
    (net (code "85") (name "Net-(U5-SEGC)") (class "Default")
      (node (ref "T4") (pin "COL4") (pinfunction "COL4_COL4") (pintype "bidirectional"))
      (node (ref "U5") (pin "20") (pinfunction "SEGC_20") (pintype "input"))
    )
    (net (code "86") (name "Net-(U5-SEGD)") (class "Default")
      (node (ref "T4") (pin "COL5") (pinfunction "COL5_COL5") (pintype "bidirectional"))
      (node (ref "U5") (pin "23") (pinfunction "SEGD_23") (pintype "input"))
    )
    (net (code "87") (name "Net-(U5-SEGE)") (class "Default")
      (node (ref "T4") (pin "COL6") (pinfunction "COL6_COL6") (pintype "bidirectional"))
      (node (ref "U5") (pin "21") (pinfunction "SEGE_21") (pintype "input"))
    )
    (net (code "88") (name "Net-(U5-SEGF)") (class "Default")
      (node (ref "T4") (pin "COL7") (pinfunction "COL7_COL7") (pintype "bidirectional"))
      (node (ref "U5") (pin "15") (pinfunction "SEGF_15") (pintype "input"))
    )
    (net (code "89") (name "Net-(U5-SEGG)") (class "Default")
      (node (ref "T4") (pin "COL8") (pinfunction "COL8_COL8") (pintype "bidirectional"))
      (node (ref "U5") (pin "17") (pinfunction "SEGG_17") (pintype "input"))
    )
    (net (code "90") (name "Net-(U5-SEGH)") (class "Default")
      (node (ref "T4") (pin "COL1") (pinfunction "COL1_COL1") (pintype "bidirectional"))
      (node (ref "U5") (pin "22") (pinfunction "SEGH_22") (pintype "input"))
    )
    (net (code "91") (name "Net-(U6-DIG0)") (class "Default")
      (node (ref "T5") (pin "COL1") (pinfunction "COL1_COL1") (pintype "bidirectional"))
      (node (ref "U6") (pin "2") (pinfunction "DIG0_2") (pintype "input"))
    )
    (net (code "92") (name "Net-(U6-DIG1)") (class "Default")
      (node (ref "T5") (pin "COL2") (pinfunction "COL2_COL2") (pintype "bidirectional"))
      (node (ref "U6") (pin "11") (pinfunction "DIG1_11") (pintype "input"))
    )
    (net (code "93") (name "Net-(U6-DIG2)") (class "Default")
      (node (ref "T5") (pin "COL3") (pinfunction "COL3_COL3") (pintype "bidirectional"))
      (node (ref "U6") (pin "6") (pinfunction "DIG2_6") (pintype "input"))
    )
    (net (code "94") (name "Net-(U6-DIG3)") (class "Default")
      (node (ref "T5") (pin "COL4") (pinfunction "COL4_COL4") (pintype "bidirectional"))
      (node (ref "U6") (pin "7") (pinfunction "DIG3_7") (pintype "input"))
    )
    (net (code "95") (name "Net-(U6-DIG4)") (class "Default")
      (node (ref "T5") (pin "COL5") (pinfunction "COL5_COL5") (pintype "bidirectional"))
      (node (ref "U6") (pin "3") (pinfunction "DIG4_3") (pintype "input"))
    )
    (net (code "96") (name "Net-(U6-DIG5)") (class "Default")
      (node (ref "T5") (pin "COL6") (pinfunction "COL6_COL6") (pintype "bidirectional"))
      (node (ref "U6") (pin "10") (pinfunction "DIG5_10") (pintype "input"))
    )
    (net (code "97") (name "Net-(U6-DIG6)") (class "Default")
      (node (ref "T5") (pin "COL7") (pinfunction "COL7_COL7") (pintype "bidirectional"))
      (node (ref "U6") (pin "5") (pinfunction "DIG6_5") (pintype "input"))
    )
    (net (code "98") (name "Net-(U6-DIG7)") (class "Default")
      (node (ref "T5") (pin "COL8") (pinfunction "COL8_COL8") (pintype "bidirectional"))
      (node (ref "U6") (pin "8") (pinfunction "DIG7_8") (pintype "input"))
    )
    (net (code "99") (name "Net-(U6-ISET)") (class "Default")
      (node (ref "R5") (pin "2") (pinfunction "2_2") (pintype "bidirectional"))
      (node (ref "U6") (pin "18") (pinfunction "ISET_18") (pintype "input"))
    )
    (net (code "100") (name "Net-(U6-SEGA)") (class "Default")
      (node (ref "T5") (pin "ROW2") (pinfunction "ROW2_ROW2") (pintype "bidirectional"))
      (node (ref "U6") (pin "14") (pinfunction "SEGA_14") (pintype "input"))
    )
    (net (code "101") (name "Net-(U6-SEGB)") (class "Default")
      (node (ref "T5") (pin "ROW3") (pinfunction "ROW3_ROW3") (pintype "bidirectional"))
      (node (ref "U6") (pin "16") (pinfunction "SEGB_16") (pintype "input"))
    )
    (net (code "102") (name "Net-(U6-SEGC)") (class "Default")
      (node (ref "T5") (pin "ROW4") (pinfunction "ROW4_ROW4") (pintype "bidirectional"))
      (node (ref "U6") (pin "20") (pinfunction "SEGC_20") (pintype "input"))
    )
    (net (code "103") (name "Net-(U6-SEGD)") (class "Default")
      (node (ref "T5") (pin "ROW5") (pinfunction "ROW5_ROW5") (pintype "bidirectional"))
      (node (ref "U6") (pin "23") (pinfunction "SEGD_23") (pintype "input"))
    )
    (net (code "104") (name "Net-(U6-SEGE)") (class "Default")
      (node (ref "T5") (pin "ROW6") (pinfunction "ROW6_ROW6") (pintype "bidirectional"))
      (node (ref "U6") (pin "21") (pinfunction "SEGE_21") (pintype "input"))
    )
    (net (code "105") (name "Net-(U6-SEGF)") (class "Default")
      (node (ref "T5") (pin "ROW7") (pinfunction "ROW7_ROW7") (pintype "bidirectional"))
      (node (ref "U6") (pin "15") (pinfunction "SEGF_15") (pintype "input"))
    )
    (net (code "106") (name "Net-(U6-SEGG)") (class "Default")
      (node (ref "T5") (pin "ROW8") (pinfunction "ROW8_ROW8") (pintype "bidirectional"))
      (node (ref "U6") (pin "17") (pinfunction "SEGG_17") (pintype "input"))
    )
    (net (code "107") (name "Net-(U6-SEGH)") (class "Default")
      (node (ref "T5") (pin "ROW1") (pinfunction "ROW1_ROW1") (pintype "bidirectional"))
      (node (ref "U6") (pin "22") (pinfunction "SEGH_22") (pintype "input"))
    )
    (net (code "108") (name "Net-(U7-DIG0)") (class "Default")
      (node (ref "T6") (pin "COL1") (pinfunction "COL1_COL1") (pintype "bidirectional"))
      (node (ref "U7") (pin "2") (pinfunction "DIG0_2") (pintype "input"))
    )
    (net (code "109") (name "Net-(U7-DIG1)") (class "Default")
      (node (ref "T6") (pin "COL2") (pinfunction "COL2_COL2") (pintype "bidirectional"))
      (node (ref "U7") (pin "11") (pinfunction "DIG1_11") (pintype "input"))
    )
    (net (code "110") (name "Net-(U7-DIG2)") (class "Default")
      (node (ref "T6") (pin "COL3") (pinfunction "COL3_COL3") (pintype "bidirectional"))
      (node (ref "U7") (pin "6") (pinfunction "DIG2_6") (pintype "input"))
    )
    (net (code "111") (name "Net-(U7-DIG3)") (class "Default")
      (node (ref "T6") (pin "COL4") (pinfunction "COL4_COL4") (pintype "bidirectional"))
      (node (ref "U7") (pin "7") (pinfunction "DIG3_7") (pintype "input"))
    )
    (net (code "112") (name "Net-(U7-DIG4)") (class "Default")
      (node (ref "T6") (pin "COL5") (pinfunction "COL5_COL5") (pintype "bidirectional"))
      (node (ref "U7") (pin "3") (pinfunction "DIG4_3") (pintype "input"))
    )
    (net (code "113") (name "Net-(U7-DIG5)") (class "Default")
      (node (ref "T6") (pin "COL6") (pinfunction "COL6_COL6") (pintype "bidirectional"))
      (node (ref "U7") (pin "10") (pinfunction "DIG5_10") (pintype "input"))
    )
    (net (code "114") (name "Net-(U7-DIG6)") (class "Default")
      (node (ref "T6") (pin "COL7") (pinfunction "COL7_COL7") (pintype "bidirectional"))
      (node (ref "U7") (pin "5") (pinfunction "DIG6_5") (pintype "input"))
    )
    (net (code "115") (name "Net-(U7-DIG7)") (class "Default")
      (node (ref "T6") (pin "COL8") (pinfunction "COL8_COL8") (pintype "bidirectional"))
      (node (ref "U7") (pin "8") (pinfunction "DIG7_8") (pintype "input"))
    )
    (net (code "116") (name "Net-(U7-ISET)") (class "Default")
      (node (ref "R7") (pin "2") (pinfunction "2_2") (pintype "bidirectional"))
      (node (ref "U7") (pin "18") (pinfunction "ISET_18") (pintype "input"))
    )
    (net (code "117") (name "Net-(U7-SEGA)") (class "Default")
      (node (ref "T6") (pin "ROW2") (pinfunction "ROW2_ROW2") (pintype "bidirectional"))
      (node (ref "U7") (pin "14") (pinfunction "SEGA_14") (pintype "input"))
    )
    (net (code "118") (name "Net-(U7-SEGB)") (class "Default")
      (node (ref "T6") (pin "ROW3") (pinfunction "ROW3_ROW3") (pintype "bidirectional"))
      (node (ref "U7") (pin "16") (pinfunction "SEGB_16") (pintype "input"))
    )
    (net (code "119") (name "Net-(U7-SEGC)") (class "Default")
      (node (ref "T6") (pin "ROW4") (pinfunction "ROW4_ROW4") (pintype "bidirectional"))
      (node (ref "U7") (pin "20") (pinfunction "SEGC_20") (pintype "input"))
    )
    (net (code "120") (name "Net-(U7-SEGD)") (class "Default")
      (node (ref "T6") (pin "ROW5") (pinfunction "ROW5_ROW5") (pintype "bidirectional"))
      (node (ref "U7") (pin "23") (pinfunction "SEGD_23") (pintype "input"))
    )
    (net (code "121") (name "Net-(U7-SEGE)") (class "Default")
      (node (ref "T6") (pin "ROW6") (pinfunction "ROW6_ROW6") (pintype "bidirectional"))
      (node (ref "U7") (pin "21") (pinfunction "SEGE_21") (pintype "input"))
    )
    (net (code "122") (name "Net-(U7-SEGF)") (class "Default")
      (node (ref "T6") (pin "ROW7") (pinfunction "ROW7_ROW7") (pintype "bidirectional"))
      (node (ref "U7") (pin "15") (pinfunction "SEGF_15") (pintype "input"))
    )
    (net (code "123") (name "Net-(U7-SEGG)") (class "Default")
      (node (ref "T6") (pin "ROW8") (pinfunction "ROW8_ROW8") (pintype "bidirectional"))
      (node (ref "U7") (pin "17") (pinfunction "SEGG_17") (pintype "input"))
    )
    (net (code "124") (name "Net-(U7-SEGH)") (class "Default")
      (node (ref "T6") (pin "ROW1") (pinfunction "ROW1_ROW1") (pintype "bidirectional"))
      (node (ref "U7") (pin "22") (pinfunction "SEGH_22") (pintype "input"))
    )
    (net (code "125") (name "Net-(U8-DIG0)") (class "Default")
      (node (ref "T7") (pin "COL1") (pinfunction "COL1_COL1") (pintype "bidirectional"))
      (node (ref "U8") (pin "2") (pinfunction "DIG0_2") (pintype "input"))
    )
    (net (code "126") (name "Net-(U8-DIG1)") (class "Default")
      (node (ref "T7") (pin "COL2") (pinfunction "COL2_COL2") (pintype "bidirectional"))
      (node (ref "U8") (pin "11") (pinfunction "DIG1_11") (pintype "input"))
    )
    (net (code "127") (name "Net-(U8-DIG2)") (class "Default")
      (node (ref "T7") (pin "COL3") (pinfunction "COL3_COL3") (pintype "bidirectional"))
      (node (ref "U8") (pin "6") (pinfunction "DIG2_6") (pintype "input"))
    )
    (net (code "128") (name "Net-(U8-DIG3)") (class "Default")
      (node (ref "T7") (pin "COL4") (pinfunction "COL4_COL4") (pintype "bidirectional"))
      (node (ref "U8") (pin "7") (pinfunction "DIG3_7") (pintype "input"))
    )
    (net (code "129") (name "Net-(U8-DIG4)") (class "Default")
      (node (ref "T7") (pin "COL5") (pinfunction "COL5_COL5") (pintype "bidirectional"))
      (node (ref "U8") (pin "3") (pinfunction "DIG4_3") (pintype "input"))
    )
    (net (code "130") (name "Net-(U8-DIG5)") (class "Default")
      (node (ref "T7") (pin "COL6") (pinfunction "COL6_COL6") (pintype "bidirectional"))
      (node (ref "U8") (pin "10") (pinfunction "DIG5_10") (pintype "input"))
    )
    (net (code "131") (name "Net-(U8-DIG6)") (class "Default")
      (node (ref "T7") (pin "COL7") (pinfunction "COL7_COL7") (pintype "bidirectional"))
      (node (ref "U8") (pin "5") (pinfunction "DIG6_5") (pintype "input"))
    )
    (net (code "132") (name "Net-(U8-DIG7)") (class "Default")
      (node (ref "T7") (pin "COL8") (pinfunction "COL8_COL8") (pintype "bidirectional"))
      (node (ref "U8") (pin "8") (pinfunction "DIG7_8") (pintype "input"))
    )
    (net (code "133") (name "Net-(U8-ISET)") (class "Default")
      (node (ref "R6") (pin "2") (pinfunction "2_2") (pintype "bidirectional"))
      (node (ref "U8") (pin "18") (pinfunction "ISET_18") (pintype "input"))
    )
    (net (code "134") (name "Net-(U8-SEGA)") (class "Default")
      (node (ref "T7") (pin "ROW2") (pinfunction "ROW2_ROW2") (pintype "bidirectional"))
      (node (ref "U8") (pin "14") (pinfunction "SEGA_14") (pintype "input"))
    )
    (net (code "135") (name "Net-(U8-SEGB)") (class "Default")
      (node (ref "T7") (pin "ROW3") (pinfunction "ROW3_ROW3") (pintype "bidirectional"))
      (node (ref "U8") (pin "16") (pinfunction "SEGB_16") (pintype "input"))
    )
    (net (code "136") (name "Net-(U8-SEGC)") (class "Default")
      (node (ref "T7") (pin "ROW4") (pinfunction "ROW4_ROW4") (pintype "bidirectional"))
      (node (ref "U8") (pin "20") (pinfunction "SEGC_20") (pintype "input"))
    )
    (net (code "137") (name "Net-(U8-SEGD)") (class "Default")
      (node (ref "T7") (pin "ROW5") (pinfunction "ROW5_ROW5") (pintype "bidirectional"))
      (node (ref "U8") (pin "23") (pinfunction "SEGD_23") (pintype "input"))
    )
    (net (code "138") (name "Net-(U8-SEGE)") (class "Default")
      (node (ref "T7") (pin "ROW6") (pinfunction "ROW6_ROW6") (pintype "bidirectional"))
      (node (ref "U8") (pin "21") (pinfunction "SEGE_21") (pintype "input"))
    )
    (net (code "139") (name "Net-(U8-SEGF)") (class "Default")
      (node (ref "T7") (pin "ROW7") (pinfunction "ROW7_ROW7") (pintype "bidirectional"))
      (node (ref "U8") (pin "15") (pinfunction "SEGF_15") (pintype "input"))
    )
    (net (code "140") (name "Net-(U8-SEGG)") (class "Default")
      (node (ref "T7") (pin "ROW8") (pinfunction "ROW8_ROW8") (pintype "bidirectional"))
      (node (ref "U8") (pin "17") (pinfunction "SEGG_17") (pintype "input"))
    )
    (net (code "141") (name "Net-(U8-SEGH)") (class "Default")
      (node (ref "T7") (pin "ROW1") (pinfunction "ROW1_ROW1") (pintype "bidirectional"))
      (node (ref "U8") (pin "22") (pinfunction "SEGH_22") (pintype "input"))
    )
    (net (code "142") (name "Net-(U9-DIG0)") (class "Default")
      (node (ref "T8") (pin "COL1") (pinfunction "COL1_COL1") (pintype "bidirectional"))
      (node (ref "U9") (pin "2") (pinfunction "DIG0_2") (pintype "input"))
    )
    (net (code "143") (name "Net-(U9-DIG1)") (class "Default")
      (node (ref "T8") (pin "COL2") (pinfunction "COL2_COL2") (pintype "bidirectional"))
      (node (ref "U9") (pin "11") (pinfunction "DIG1_11") (pintype "input"))
    )
    (net (code "144") (name "Net-(U9-DIG2)") (class "Default")
      (node (ref "T8") (pin "COL3") (pinfunction "COL3_COL3") (pintype "bidirectional"))
      (node (ref "U9") (pin "6") (pinfunction "DIG2_6") (pintype "input"))
    )
    (net (code "145") (name "Net-(U9-DIG3)") (class "Default")
      (node (ref "T8") (pin "COL4") (pinfunction "COL4_COL4") (pintype "bidirectional"))
      (node (ref "U9") (pin "7") (pinfunction "DIG3_7") (pintype "input"))
    )
    (net (code "146") (name "Net-(U9-DIG4)") (class "Default")
      (node (ref "T8") (pin "COL5") (pinfunction "COL5_COL5") (pintype "bidirectional"))
      (node (ref "U9") (pin "3") (pinfunction "DIG4_3") (pintype "input"))
    )
    (net (code "147") (name "Net-(U9-DIG5)") (class "Default")
      (node (ref "T8") (pin "COL6") (pinfunction "COL6_COL6") (pintype "bidirectional"))
      (node (ref "U9") (pin "10") (pinfunction "DIG5_10") (pintype "input"))
    )
    (net (code "148") (name "Net-(U9-DIG6)") (class "Default")
      (node (ref "T8") (pin "COL7") (pinfunction "COL7_COL7") (pintype "bidirectional"))
      (node (ref "U9") (pin "5") (pinfunction "DIG6_5") (pintype "input"))
    )
    (net (code "149") (name "Net-(U9-DIG7)") (class "Default")
      (node (ref "T8") (pin "COL8") (pinfunction "COL8_COL8") (pintype "bidirectional"))
      (node (ref "U9") (pin "8") (pinfunction "DIG7_8") (pintype "input"))
    )
    (net (code "150") (name "Net-(U9-ISET)") (class "Default")
      (node (ref "R8") (pin "2") (pinfunction "2_2") (pintype "bidirectional"))
      (node (ref "U9") (pin "18") (pinfunction "ISET_18") (pintype "input"))
    )
    (net (code "151") (name "Net-(U9-SEGA)") (class "Default")
      (node (ref "T8") (pin "ROW2") (pinfunction "ROW2_ROW2") (pintype "bidirectional"))
      (node (ref "U9") (pin "14") (pinfunction "SEGA_14") (pintype "input"))
    )
    (net (code "152") (name "Net-(U9-SEGB)") (class "Default")
      (node (ref "T8") (pin "ROW3") (pinfunction "ROW3_ROW3") (pintype "bidirectional"))
      (node (ref "U9") (pin "16") (pinfunction "SEGB_16") (pintype "input"))
    )
    (net (code "153") (name "Net-(U9-SEGC)") (class "Default")
      (node (ref "T8") (pin "ROW4") (pinfunction "ROW4_ROW4") (pintype "bidirectional"))
      (node (ref "U9") (pin "20") (pinfunction "SEGC_20") (pintype "input"))
    )
    (net (code "154") (name "Net-(U9-SEGD)") (class "Default")
      (node (ref "T8") (pin "ROW5") (pinfunction "ROW5_ROW5") (pintype "bidirectional"))
      (node (ref "U9") (pin "23") (pinfunction "SEGD_23") (pintype "input"))
    )
    (net (code "155") (name "Net-(U9-SEGE)") (class "Default")
      (node (ref "T8") (pin "ROW6") (pinfunction "ROW6_ROW6") (pintype "bidirectional"))
      (node (ref "U9") (pin "21") (pinfunction "SEGE_21") (pintype "input"))
    )
    (net (code "156") (name "Net-(U9-SEGF)") (class "Default")
      (node (ref "T8") (pin "ROW7") (pinfunction "ROW7_ROW7") (pintype "bidirectional"))
      (node (ref "U9") (pin "15") (pinfunction "SEGF_15") (pintype "input"))
    )
    (net (code "157") (name "Net-(U9-SEGG)") (class "Default")
      (node (ref "T8") (pin "ROW8") (pinfunction "ROW8_ROW8") (pintype "bidirectional"))
      (node (ref "U9") (pin "17") (pinfunction "SEGG_17") (pintype "input"))
    )
    (net (code "158") (name "Net-(U9-SEGH)") (class "Default")
      (node (ref "T8") (pin "ROW1") (pinfunction "ROW1_ROW1") (pintype "bidirectional"))
      (node (ref "U9") (pin "22") (pinfunction "SEGH_22") (pintype "input"))
    )
    (net (code "159") (name "RESET") (class "Default")
      (node (ref "C2") (pin "2") (pinfunction "2_2") (pintype "bidirectional"))
      (node (ref "MCU") (pin "29") (pinfunction "PC6(/RESET)_29") (pintype "bidirectional"))
      (node (ref "R10") (pin "1") (pinfunction "1_1") (pintype "bidirectional"))
      (node (ref "SV1") (pin "2") (pinfunction "2_2") (pintype "passive"))
      (node (ref "U$1") (pin "P$2") (pinfunction "S_P$2") (pintype "passive"))
    )
    (net (code "160") (name "RXD") (class "Default")
      (node (ref "MCU") (pin "30") (pinfunction "PD0(RXD)_30") (pintype "bidirectional"))
      (node (ref "SV2") (pin "2") (pinfunction "2_2") (pintype "passive"))
    )
    (net (code "161") (name "SCK") (class "Default")
      (node (ref "MCU") (pin "17") (pinfunction "PB5(SCK)_17") (pintype "bidirectional"))
      (node (ref "R11") (pin "1") (pinfunction "1_1") (pintype "bidirectional"))
      (node (ref "SV1") (pin "4") (pinfunction "4_4") (pintype "passive"))
    )
    (net (code "162") (name "SCL") (class "Default")
      (node (ref "MCU") (pin "28") (pinfunction "PC5(ADC5/SCL)_28") (pintype "bidirectional"))
    )
    (net (code "163") (name "SDA") (class "Default")
      (node (ref "MCU") (pin "27") (pinfunction "PC4(ADC4/SDA)_27") (pintype "bidirectional"))
    )
    (net (code "164") (name "SS") (class "Default")
      (node (ref "MCU") (pin "14") (pinfunction "PB2(SS/OC1B)_14") (pintype "bidirectional"))
    )
    (net (code "165") (name "TXD") (class "Default")
      (node (ref "MCU") (pin "31") (pinfunction "PD1(TXD)_31") (pintype "bidirectional"))
      (node (ref "SV2") (pin "3") (pinfunction "3_3") (pintype "passive"))
    )
    (net (code "166") (name "U2OUT") (class "Default")
      (node (ref "U2") (pin "24") (pinfunction "DOUT_24") (pintype "input"))
      (node (ref "U3") (pin "1") (pinfunction "DIN_1") (pintype "input"))
    )
    (net (code "167") (name "U3OUT") (class "Default")
      (node (ref "U3") (pin "24") (pinfunction "DOUT_24") (pintype "input"))
      (node (ref "U4") (pin "1") (pinfunction "DIN_1") (pintype "input"))
    )
    (net (code "168") (name "U4OUT") (class "Default")
      (node (ref "U4") (pin "24") (pinfunction "DOUT_24") (pintype "input"))
      (node (ref "U5") (pin "1") (pinfunction "DIN_1") (pintype "input"))
    )
    (net (code "169") (name "U6OUT") (class "Default")
      (node (ref "U6") (pin "24") (pinfunction "DOUT_24") (pintype "input"))
      (node (ref "U7") (pin "1") (pinfunction "DIN_1") (pintype "input"))
    )
    (net (code "170") (name "U7OUT") (class "Default")
      (node (ref "U7") (pin "24") (pinfunction "DOUT_24") (pintype "input"))
      (node (ref "U8") (pin "1") (pinfunction "DIN_1") (pintype "input"))
    )
    (net (code "171") (name "U8OUT") (class "Default")
      (node (ref "U8") (pin "24") (pinfunction "DOUT_24") (pintype "input"))
      (node (ref "U9") (pin "1") (pinfunction "DIN_1") (pintype "input"))
    )
    (net (code "172") (name "X1") (class "Default")
      (node (ref "C3") (pin "2") (pinfunction "2_2") (pintype "bidirectional"))
      (node (ref "MCU") (pin "7") (pinfunction "PB6(XTAL1/TOSC1)_7") (pintype "bidirectional"))
      (node (ref "Y1") (pin "2") (pinfunction "2_2") (pintype "passive"))
    )
    (net (code "173") (name "X2") (class "Default")
      (node (ref "C4") (pin "2") (pinfunction "2_2") (pintype "bidirectional"))
      (node (ref "MCU") (pin "8") (pinfunction "PB7(XTAL2/TOSC2)_8") (pintype "bidirectional"))
      (node (ref "Y1") (pin "1") (pinfunction "1_1") (pintype "passive"))
    )
    (net (code "174") (name "unconnected-(U5-DOUT-Pad24)") (class "Default")
      (node (ref "U5") (pin "24") (pinfunction "DOUT_24") (pintype "input"))
    )
    (net (code "175") (name "unconnected-(U9-DOUT-Pad24)") (class "Default")
      (node (ref "U9") (pin "24") (pinfunction "DOUT_24") (pintype "input"))
    )
    (net (code "176") (name "unconnected-(USB1-DM-Pad2)") (class "Default")
      (node (ref "USB1") (pin "2") (pinfunction "DM_2") (pintype "bidirectional"))
    )
    (net (code "177") (name "unconnected-(USB1-DP-Pad3)") (class "Default")
      (node (ref "USB1") (pin "3") (pinfunction "DP_3") (pintype "bidirectional"))
    )
    (net (code "178") (name "unconnected-(USB1-ID-Pad4)") (class "Default")
      (node (ref "USB1") (pin "4") (pinfunction "ID_4") (pintype "bidirectional"))
    )
  )
)
